# 04_Schematic.net
KiCad netlist of a schematic drawn in Altium Designer
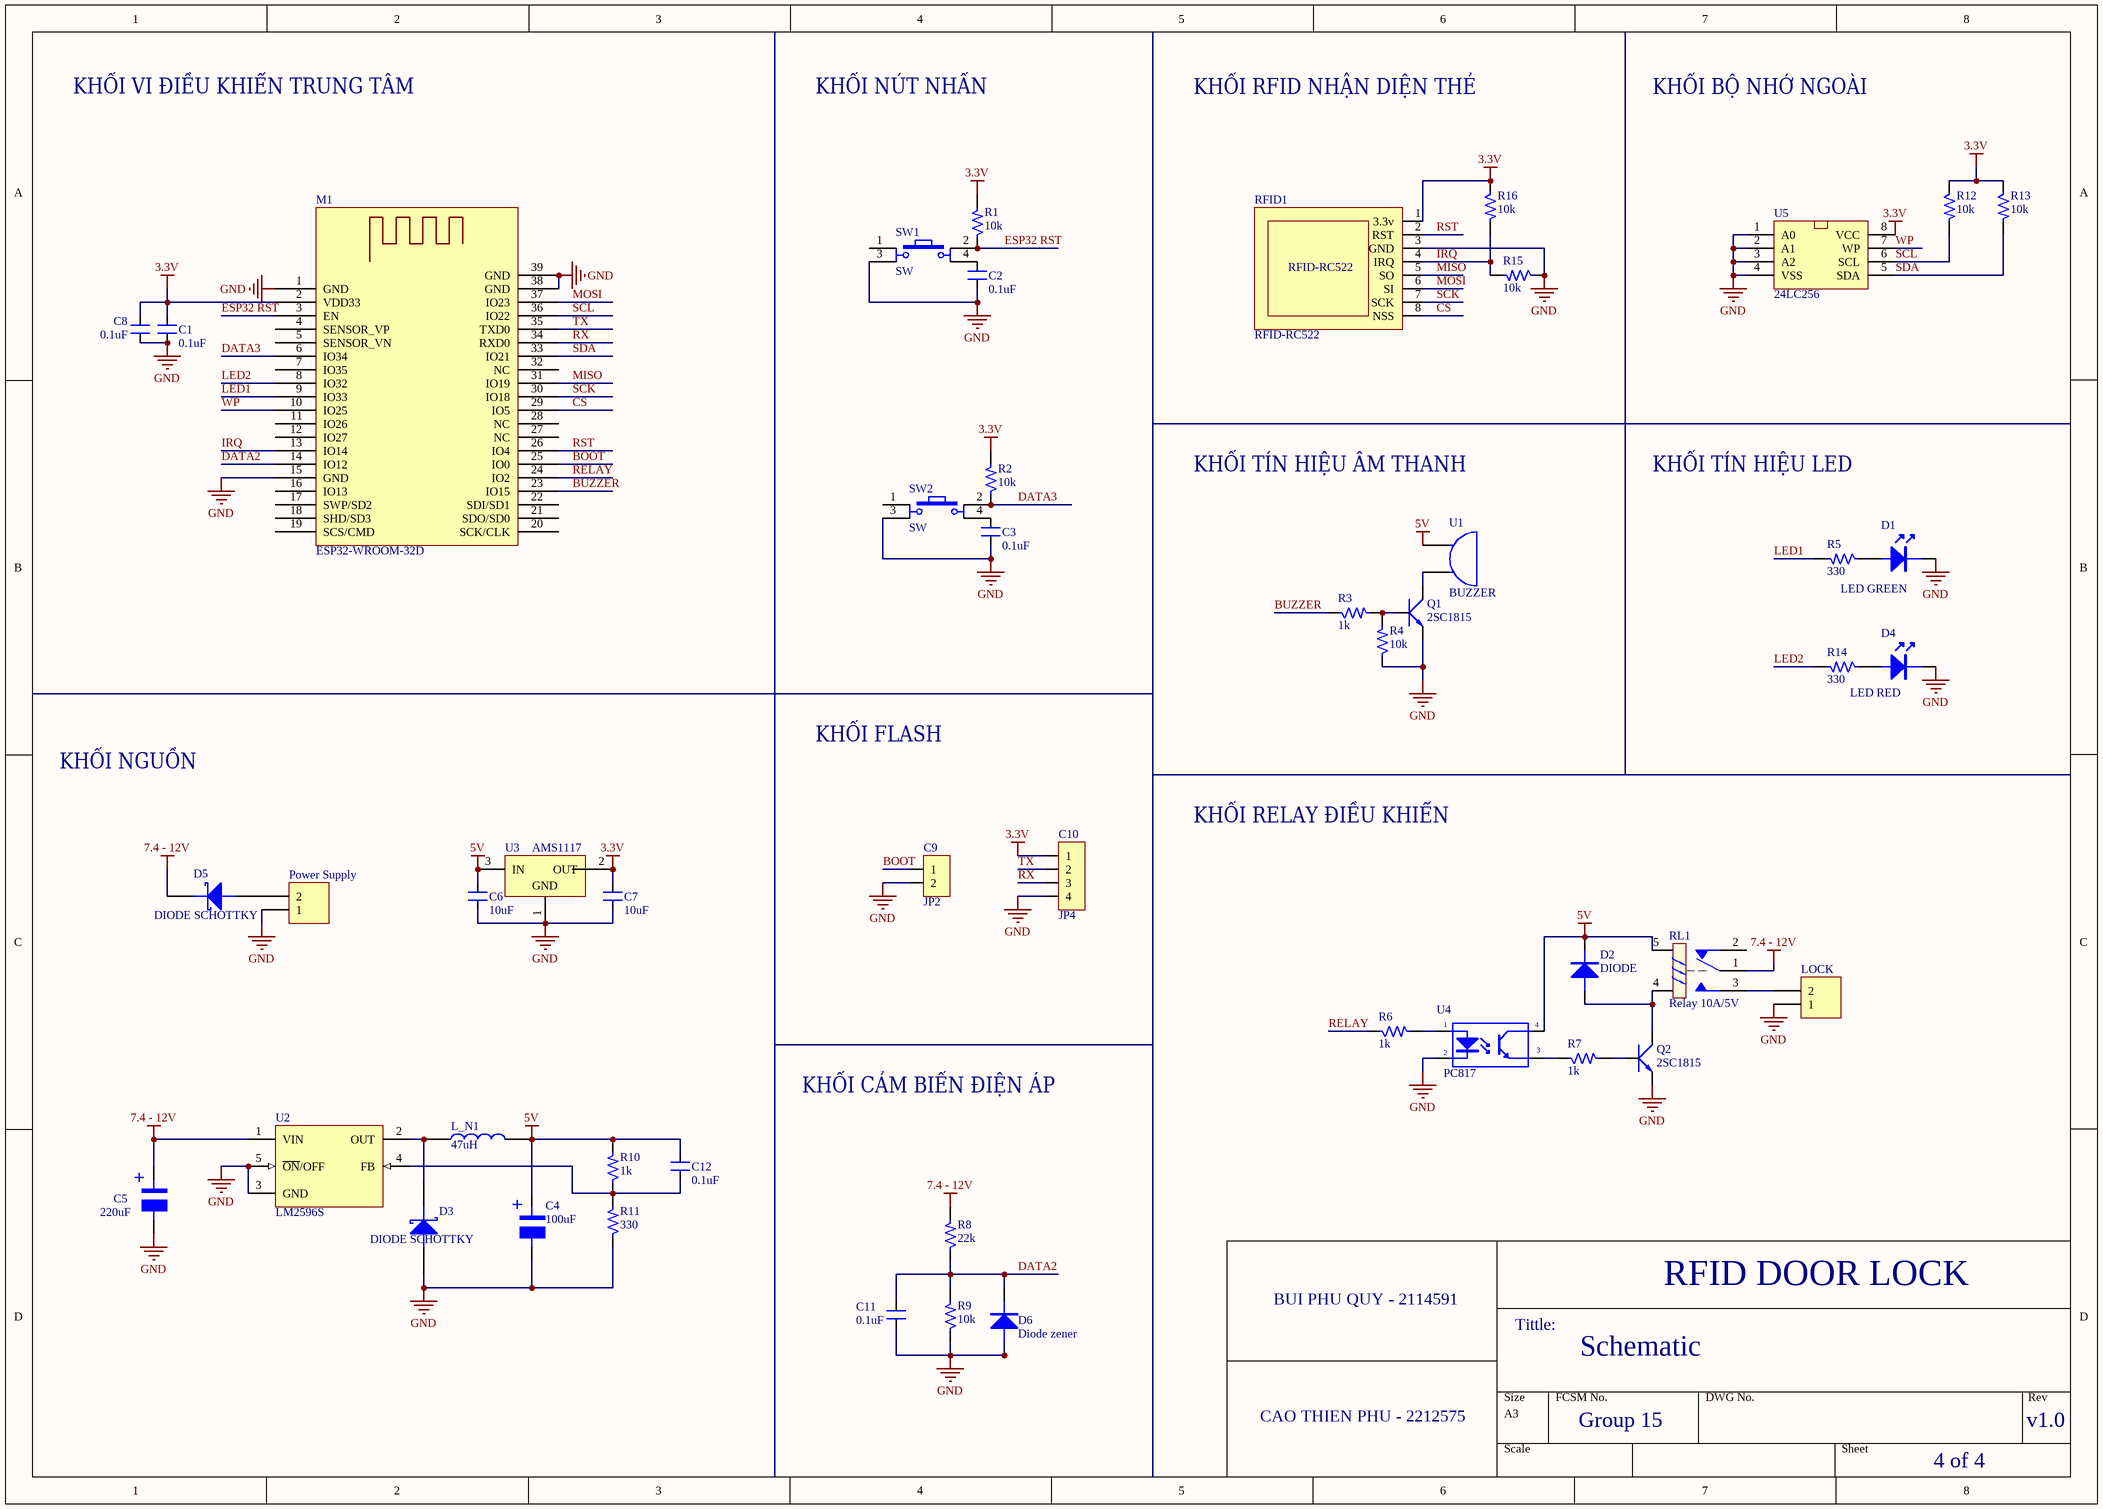
[diagram p0: 04.Schematic.SchDoc]

(export (version "E")
  (design (tool "Eeschema 10.0.6"))
  (components
    (comp (ref "C1")
      (value "0.1uF")
      (footprint "SMD CAP 0805")
      (description "Cap np W0.4")
      (libsource (lib "KhanhBK_Library_4") (part "CN4"))
    )
    (comp (ref "C2")
      (value "0.1uF")
      (footprint "SMD CAP 0805")
      (description "Cap np W0.4")
      (libsource (lib "KhanhBK_Library_4") (part "CN4"))
    )
    (comp (ref "C3")
      (value "0.1uF")
      (footprint "SMD CAP 0805")
      (description "Cap np W0.4")
      (libsource (lib "KhanhBK_Library_4") (part "CN4"))
    )
    (comp (ref "C4")
      (value "100uF")
      (footprint "Cty1:100UF/16V_SMD")
      (libsource (lib "Devzone_SCHLib") (part "Cap100uF_SMD"))
    )
    (comp (ref "C5")
      (value "220uF")
      (footprint "Cty1:100UF/16V_SMD")
      (libsource (lib "Devzone_SCHLib") (part "Cap100uF_SMD"))
    )
    (comp (ref "C6")
      (value "10uF")
      (footprint "SMD CAP 0805")
      (description "Cap np W0.4")
      (libsource (lib "KhanhBK_Library_4") (part "CN4"))
    )
    (comp (ref "C7")
      (value "10uF")
      (footprint "SMD CAP 0805")
      (description "Cap np W0.4")
      (libsource (lib "KhanhBK_Library_4") (part "CN4"))
    )
    (comp (ref "C8")
      (value "0.1uF")
      (footprint "SMD CAP 0805")
      (description "Cap np W0.4")
      (libsource (lib "KhanhBK_Library_4") (part "CN4"))
    )
    (comp (ref "C9")
      (value "JP2")
      (footprint "JP2-C1T")
      (description "WR-PHD 2.54 mm Angled Socket Header")
      (fields
        (field (name "MANUFACTURER") "Würth Elektronik eiSos GmbH")
        (field (name "PARTNO") "613002143121")
        (field (name "CREATED BY") "Karrer Zheng")
      )
      (libsource (lib "KhanhBK_Library_4") (part "JP2"))
    )
    (comp (ref "C10")
      (value "JP4")
      (footprint "JP4-C1T")
      (description "WR-PHD 2.54 mm Angled Socket Header")
      (fields
        (field (name "MANUFACTURER") "Würth Elektronik eiSos GmbH")
        (field (name "PARTNO") "613004143121")
        (field (name "CREATED BY") "Karrer Zheng")
      )
      (libsource (lib "KhanhBK_Library_4") (part "JP4"))
    )
    (comp (ref "C11")
      (value "0.1uF")
      (footprint "SMD CAP 0805")
      (description "Cap np W0.4")
      (libsource (lib "KhanhBK_Library_4") (part "CN4"))
    )
    (comp (ref "C12")
      (value "0.1uF")
      (footprint "SMD CAP 0805")
      (description "Cap np W0.4")
      (libsource (lib "KhanhBK_Library_4") (part "CN4"))
    )
    (comp (ref "D1") (value "LED GREEN") (footprint "LED3mm") (libsource (lib "Devzone_SCHLib") (part "LED")))
    (comp (ref "D2")
      (value "DIODE")
      (footprint "LL4148 Diode")
      (description "Diode")
      (libsource (lib "Devzone_SCHLib") (part "DIODE"))
    )
    (comp (ref "D3")
      (value "DIODE SCHOTTKY")
      (footprint "SMD SS34")
      (description "Schottky Diode")
      (libsource (lib "Devzone_SCHLib") (part "DIODE SCHOTTKY"))
    )
    (comp (ref "D4") (value "LED RED") (footprint "LED3mm") (libsource (lib "Devzone_SCHLib") (part "LED")))
    (comp (ref "D5")
      (value "DIODE SCHOTTKY")
      (footprint "SMD SS34")
      (description "Schottky Diode")
      (libsource (lib "Devzone_SCHLib") (part "DIODE SCHOTTKY"))
    )
    (comp (ref "D6")
      (value "Diode zener")
      (footprint "LL4148 Diode")
      (description "Diode")
      (libsource (lib "Devzone_SCHLib") (part "DIODE"))
    )
    (comp (ref "LOCK")
      (value "DOMINO")
      (footprint "CON 2")
      (libsource (lib "KhanhBK_Library_4") (part "HEADER 2"))
    )
    (comp (ref "L_N1")
      (value "47uH")
      (footprint "SMD 12mmx8mm Inductor")
      (libsource (lib "Devzone_SCHLib") (part "INDUCTOR1"))
    )
    (comp (ref "M1")
      (value "ESP32-WROOM-32D")
      (footprint "ESP32-WROOM-32")
      (description "ESP32")
      (libsource (lib "KhanhBK_SCH_Lib_5") (part "WIFI_ESP32-WROVER"))
    )
    (comp (ref "Power Supply")
      (value "DOMINO")
      (footprint "CON 2")
      (libsource (lib "KhanhBK_Library_4") (part "HEADER 2"))
    )
    (comp (ref "Q1")
      (value "2SC1815")
      (footprint "SOT23-321")
      (description "NPN 600mW, ECB")
      (libsource (lib "KhanhBK_Library_4") (part "2SC1815"))
    )
    (comp (ref "Q2")
      (value "2SC1815")
      (footprint "SOT23-321")
      (description "NPN 600mW, ECB")
      (libsource (lib "KhanhBK_Library_4") (part "2SC1815"))
    )
    (comp (ref "R1")
      (value "10k")
      (footprint "SM-0805")
      (description "Resistor 1/4W")
      (libsource (lib "Devzone_SCHLib") (part "Res"))
    )
    (comp (ref "R2")
      (value "10k")
      (footprint "SM-0805")
      (description "Resistor 1/4W")
      (libsource (lib "Devzone_SCHLib") (part "Res"))
    )
    (comp (ref "R3")
      (value "1k")
      (footprint "SM-0805")
      (description "Resistor 1/4W")
      (libsource (lib "Devzone_SCHLib") (part "Res"))
    )
    (comp (ref "R4")
      (value "10k")
      (footprint "SM-0805")
      (description "Resistor 1/4W")
      (libsource (lib "Devzone_SCHLib") (part "Res"))
    )
    (comp (ref "R5")
      (value "330")
      (footprint "SM-0805")
      (description "Resistor 1/4W")
      (libsource (lib "Devzone_SCHLib") (part "Res"))
    )
    (comp (ref "R6")
      (value "1k")
      (footprint "SM-0805")
      (description "Resistor 1/4W")
      (libsource (lib "Devzone_SCHLib") (part "Res"))
    )
    (comp (ref "R7")
      (value "1k")
      (footprint "SM-0805")
      (description "Resistor 1/4W")
      (libsource (lib "Devzone_SCHLib") (part "Res"))
    )
    (comp (ref "R8")
      (value "22k")
      (footprint "SM-0805")
      (description "Resistor 1/4W")
      (libsource (lib "Devzone_SCHLib") (part "Res"))
    )
    (comp (ref "R9")
      (value "10k")
      (footprint "SM-0805")
      (description "Resistor 1/4W")
      (libsource (lib "Devzone_SCHLib") (part "Res"))
    )
    (comp (ref "R10")
      (value "1k")
      (footprint "SM-0805")
      (description "Resistor 1/4W")
      (libsource (lib "Devzone_SCHLib") (part "Res"))
    )
    (comp (ref "R11")
      (value "330")
      (footprint "SM-0805")
      (description "Resistor 1/4W")
      (libsource (lib "Devzone_SCHLib") (part "Res"))
    )
    (comp (ref "R12")
      (value "10k")
      (footprint "SM-0805")
      (description "Resistor 1/4W")
      (libsource (lib "Devzone_SCHLib") (part "Res"))
    )
    (comp (ref "R13")
      (value "10k")
      (footprint "SM-0805")
      (description "Resistor 1/4W")
      (libsource (lib "Devzone_SCHLib") (part "Res"))
    )
    (comp (ref "R14")
      (value "330")
      (footprint "SM-0805")
      (description "Resistor 1/4W")
      (libsource (lib "Devzone_SCHLib") (part "Res"))
    )
    (comp (ref "R15")
      (value "10k")
      (footprint "SM-0805")
      (description "Resistor 1/4W")
      (libsource (lib "Devzone_SCHLib") (part "Res"))
    )
    (comp (ref "R16")
      (value "10k")
      (footprint "SM-0805")
      (description "Resistor 1/4W")
      (libsource (lib "Devzone_SCHLib") (part "Res"))
    )
    (comp (ref "RFID1")
      (value "RFID-RC522")
      (footprint "RFID-RC522-BOARD")
      (libsource (lib "SCH_Lib_Devzone") (part "RFID"))
    )
    (comp (ref "RL1")
      (value "Relay 10A/5V")
      (footprint "RL_SPDT_10A")
      (description "Relay SPDT,10A - 12VDC 5 Pin")
      (libsource (lib "KhanhBK_Library_4") (part "Relay 1"))
    )
    (comp (ref "SW1")
      (value "SW")
      (footprint "SW4")
      (description "Switch button 4 pin")
      (libsource (lib "Devzone_SCHLib") (part "SW4"))
    )
    (comp (ref "SW2")
      (value "SW")
      (footprint "SW4")
      (description "Switch button 4 pin")
      (libsource (lib "Devzone_SCHLib") (part "SW4"))
    )
    (comp (ref "U1")
      (value "BUZZER")
      (footprint "BUZZER 5V")
      (description "Buzzer")
      (libsource (lib "Devzone_SCHLib") (part "BUZZER"))
    )
    (comp (ref "U2")
      (value "LM2596S")
      (footprint "TO263-5_Via40/10mil")
      (description "SIMPLE SWITCHER; 3A Step-Down Voltage Regulator")
      (fields
        (field (name "PARTNUMBER") "LM2596S-5.0")
        (field (name "MANUFACTURER") "National Semiconductor")
        (field (name "PUBLISHER") "Altium Limited")
      )
      (libsource (lib "KhanhBK_Library_4") (part "LM2596"))
    )
    (comp (ref "U3")
      (value "AMS1117")
      (footprint "SOT223")
      (libsource (lib "KhanhBK_Library_4") (part "AMS117"))
    )
    (comp (ref "U4")
      (value "PC817")
      (footprint "DIP4/W0.3")
      (description "Single Opto")
      (libsource (lib "Devzone_SCHLib") (part "PC817_1"))
    )
    (comp (ref "U5")
      (value "24LC256")
      (footprint "SOP8_L")
      (description "256KBit I2C CMOS Serial EEPROM")
      (libsource (lib "KhanhBK_SCH_Lib_5") (part "24LC256"))
    )
  )
  (nets
    (net (code "1") (name "/BOOT") (class "Default")
      (node (ref "C9") (pin "1") (pinfunction "1_1") (pintype "passive"))
      (node (ref "M1") (pin "25") (pinfunction "IO0_25") (pintype "passive"))
    )
    (net (code "2") (name "/BUZZER") (class "Default")
      (node (ref "M1") (pin "23") (pinfunction "IO15_23") (pintype "passive"))
      (node (ref "R3") (pin "1") (pinfunction "1_1") (pintype "passive"))
    )
    (net (code "3") (name "/CS") (class "Default")
      (node (ref "M1") (pin "29") (pinfunction "IO5_29") (pintype "passive"))
      (node (ref "RFID1") (pin "8") (pinfunction "NSS_8") (pintype "passive"))
    )
    (net (code "4") (name "/DATA2") (class "Default")
      (node (ref "C11") (pin "2") (pinfunction "2_2") (pintype "passive"))
      (node (ref "D6") (pin "2") (pinfunction "2_2") (pintype "passive"))
      (node (ref "M1") (pin "14") (pinfunction "IO12_14") (pintype "passive"))
      (node (ref "R8") (pin "1") (pinfunction "1_1") (pintype "passive"))
      (node (ref "R9") (pin "2") (pinfunction "2_2") (pintype "passive"))
    )
    (net (code "5") (name "/DATA3") (class "Default")
      (node (ref "M1") (pin "6") (pinfunction "IO34_6") (pintype "passive"))
      (node (ref "R2") (pin "1") (pinfunction "1_1") (pintype "passive"))
      (node (ref "SW2") (pin "2") (pintype "passive"))
    )
    (net (code "6") (name "/ESP32 RST") (class "Default")
      (node (ref "M1") (pin "3") (pinfunction "EN_3") (pintype "passive"))
      (node (ref "R1") (pin "1") (pinfunction "1_1") (pintype "passive"))
      (node (ref "SW1") (pin "2") (pintype "passive"))
    )
    (net (code "7") (name "/IRQ") (class "Default")
      (node (ref "M1") (pin "13") (pinfunction "IO14_13") (pintype "passive"))
      (node (ref "R15") (pin "2") (pinfunction "2_2") (pintype "passive"))
      (node (ref "R16") (pin "2") (pinfunction "2_2") (pintype "passive"))
      (node (ref "RFID1") (pin "4") (pinfunction "IRQ_4") (pintype "passive"))
    )
    (net (code "8") (name "/LED1") (class "Default")
      (node (ref "M1") (pin "9") (pinfunction "IO33_9") (pintype "passive"))
      (node (ref "R5") (pin "2") (pinfunction "2_2") (pintype "passive"))
    )
    (net (code "9") (name "/LED2") (class "Default")
      (node (ref "M1") (pin "8") (pinfunction "IO32_8") (pintype "passive"))
      (node (ref "R14") (pin "2") (pinfunction "2_2") (pintype "passive"))
    )
    (net (code "10") (name "/MISO") (class "Default")
      (node (ref "M1") (pin "31") (pinfunction "IO19_31") (pintype "passive"))
      (node (ref "RFID1") (pin "5") (pinfunction "SO_5") (pintype "passive"))
    )
    (net (code "11") (name "/MOSI") (class "Default")
      (node (ref "M1") (pin "37") (pinfunction "IO23_37") (pintype "passive"))
      (node (ref "RFID1") (pin "6") (pinfunction "SI_6") (pintype "passive"))
    )
    (net (code "12") (name "/RELAY") (class "Default")
      (node (ref "M1") (pin "24") (pinfunction "IO2_24") (pintype "passive"))
      (node (ref "R6") (pin "1") (pinfunction "1_1") (pintype "passive"))
    )
    (net (code "13") (name "/RST") (class "Default")
      (node (ref "M1") (pin "26") (pinfunction "IO4_26") (pintype "passive"))
      (node (ref "RFID1") (pin "2") (pinfunction "RST_2") (pintype "passive"))
    )
    (net (code "14") (name "/RX") (class "Default")
      (node (ref "C10") (pin "3") (pinfunction "3_3") (pintype "passive"))
      (node (ref "M1") (pin "34") (pinfunction "RXD0_34") (pintype "passive"))
    )
    (net (code "15") (name "/SCK") (class "Default")
      (node (ref "M1") (pin "30") (pinfunction "IO18_30") (pintype "passive"))
      (node (ref "RFID1") (pin "7") (pinfunction "SCK_7") (pintype "passive"))
    )
    (net (code "16") (name "/SCL") (class "Default")
      (node (ref "M1") (pin "36") (pinfunction "IO22_36") (pintype "passive"))
      (node (ref "R12") (pin "2") (pinfunction "2_2") (pintype "passive"))
      (node (ref "U5") (pin "6") (pinfunction "SCL_6") (pintype "passive"))
    )
    (net (code "17") (name "/SDA") (class "Default")
      (node (ref "M1") (pin "33") (pinfunction "IO21_33") (pintype "passive"))
      (node (ref "R13") (pin "2") (pinfunction "2_2") (pintype "passive"))
      (node (ref "U5") (pin "5") (pinfunction "SDA_5") (pintype "passive"))
    )
    (net (code "18") (name "/TX") (class "Default")
      (node (ref "C10") (pin "2") (pinfunction "2_2") (pintype "passive"))
      (node (ref "M1") (pin "35") (pinfunction "TXD0_35") (pintype "passive"))
    )
    (net (code "19") (name "/WP") (class "Default")
      (node (ref "M1") (pin "10") (pinfunction "IO25_10") (pintype "passive"))
      (node (ref "U5") (pin "7") (pinfunction "WP_7") (pintype "passive"))
    )
    (net (code "20") (name "3.3V") (class "Default")
      (node (ref "C1") (pin "2") (pinfunction "2_2") (pintype "passive"))
      (node (ref "C10") (pin "1") (pinfunction "1_1") (pintype "passive"))
      (node (ref "C7") (pin "2") (pinfunction "2_2") (pintype "passive"))
      (node (ref "C8") (pin "2") (pinfunction "2_2") (pintype "passive"))
      (node (ref "M1") (pin "2") (pinfunction "VDD33_2") (pintype "passive"))
      (node (ref "R1") (pin "2") (pinfunction "2_2") (pintype "passive"))
      (node (ref "R12") (pin "1") (pinfunction "1_1") (pintype "passive"))
      (node (ref "R13") (pin "1") (pinfunction "1_1") (pintype "passive"))
      (node (ref "R16") (pin "1") (pinfunction "1_1") (pintype "passive"))
      (node (ref "R2") (pin "2") (pinfunction "2_2") (pintype "passive"))
      (node (ref "RFID1") (pin "1") (pinfunction "3.3v_1") (pintype "passive"))
      (node (ref "U3") (pin "2") (pinfunction "OUT_2") (pintype "power_in"))
      (node (ref "U3") (pin "4") (pinfunction "4_4") (pintype "passive"))
      (node (ref "U5") (pin "8") (pinfunction "VCC_8") (pintype "passive"))
    )
    (net (code "21") (name "5V") (class "Default")
      (node (ref "C12") (pin "2") (pinfunction "2_2") (pintype "passive"))
      (node (ref "C4") (pin "1") (pinfunction "1_1") (pintype "passive"))
      (node (ref "C6") (pin "2") (pinfunction "2_2") (pintype "passive"))
      (node (ref "D2") (pin "2") (pinfunction "2_2") (pintype "passive"))
      (node (ref "L_N1") (pin "2") (pinfunction "2_2") (pintype "passive"))
      (node (ref "R10") (pin "2") (pinfunction "2_2") (pintype "passive"))
      (node (ref "RL1") (pin "5") (pinfunction "5_5") (pintype "passive"))
      (node (ref "U1") (pin "1") (pinfunction "A_1") (pintype "passive"))
      (node (ref "U3") (pin "3") (pinfunction "IN_3") (pintype "power_in"))
      (node (ref "U4") (pin "4") (pinfunction "C_4") (pintype "passive"))
    )
    (net (code "22") (name "7.4 - 12V") (class "Default")
      (node (ref "C5") (pin "1") (pinfunction "1_1") (pintype "passive"))
      (node (ref "D5") (pin "2") (pinfunction "K_2") (pintype "passive"))
      (node (ref "R8") (pin "2") (pinfunction "2_2") (pintype "passive"))
      (node (ref "RL1") (pin "1") (pinfunction "1_1") (pintype "passive"))
      (node (ref "U2") (pin "1") (pinfunction "VIN_1") (pintype "power_in"))
    )
    (net (code "23") (name "GND") (class "Default")
      (node (ref "C1") (pin "1") (pinfunction "1_1") (pintype "passive"))
      (node (ref "C10") (pin "4") (pinfunction "4_4") (pintype "passive"))
      (node (ref "C11") (pin "1") (pinfunction "1_1") (pintype "passive"))
      (node (ref "C2") (pin "1") (pinfunction "1_1") (pintype "passive"))
      (node (ref "C3") (pin "1") (pinfunction "1_1") (pintype "passive"))
      (node (ref "C4") (pin "2") (pinfunction "2_2") (pintype "passive"))
      (node (ref "C5") (pin "2") (pinfunction "2_2") (pintype "passive"))
      (node (ref "C6") (pin "1") (pinfunction "1_1") (pintype "passive"))
      (node (ref "C7") (pin "1") (pinfunction "1_1") (pintype "passive"))
      (node (ref "C8") (pin "1") (pinfunction "1_1") (pintype "passive"))
      (node (ref "C9") (pin "2") (pinfunction "2_2") (pintype "passive"))
      (node (ref "D1") (pin "2") (pinfunction "2_2") (pintype "passive"))
      (node (ref "D3") (pin "1") (pinfunction "A_1") (pintype "passive"))
      (node (ref "D4") (pin "2") (pinfunction "2_2") (pintype "passive"))
      (node (ref "D6") (pin "1") (pinfunction "1_1") (pintype "passive"))
      (node (ref "LOCK") (pin "1") (pinfunction "1_1") (pintype "passive"))
      (node (ref "M1") (pin "1") (pinfunction "GND_1") (pintype "passive"))
      (node (ref "M1") (pin "15") (pinfunction "GND_15") (pintype "passive"))
      (node (ref "M1") (pin "38") (pinfunction "GND_38") (pintype "passive"))
      (node (ref "M1") (pin "39") (pinfunction "GND_39") (pintype "passive"))
      (node (ref "Power Supply") (pin "1") (pinfunction "1_1") (pintype "passive"))
      (node (ref "Q1") (pin "1") (pinfunction "E_1") (pintype "passive"))
      (node (ref "Q2") (pin "1") (pinfunction "E_1") (pintype "passive"))
      (node (ref "R11") (pin "1") (pinfunction "1_1") (pintype "passive"))
      (node (ref "R15") (pin "1") (pinfunction "1_1") (pintype "passive"))
      (node (ref "R4") (pin "1") (pinfunction "1_1") (pintype "passive"))
      (node (ref "R9") (pin "1") (pinfunction "1_1") (pintype "passive"))
      (node (ref "RFID1") (pin "3") (pinfunction "GND_3") (pintype "passive"))
      (node (ref "SW1") (pin "3") (pintype "passive"))
      (node (ref "SW2") (pin "3") (pintype "passive"))
      (node (ref "U2") (pin "3") (pinfunction "GND_3") (pintype "power_in"))
      (node (ref "U2") (pin "5") (pinfunction "~{ON}/OFF_5") (pintype "input"))
      (node (ref "U3") (pin "1") (pinfunction "GND_1") (pintype "power_in"))
      (node (ref "U4") (pin "2") (pinfunction "K_2") (pintype "passive"))
      (node (ref "U5") (pin "1") (pinfunction "A0_1") (pintype "passive"))
      (node (ref "U5") (pin "2") (pinfunction "A1_2") (pintype "passive"))
      (node (ref "U5") (pin "3") (pinfunction "A2_3") (pintype "passive"))
      (node (ref "U5") (pin "4") (pinfunction "VSS_4") (pintype "passive"))
    )
    (net (code "24") (name "Net-(C2-Pad2)") (class "Default")
      (node (ref "C2") (pin "2") (pinfunction "2_2") (pintype "passive"))
      (node (ref "SW1") (pin "4") (pintype "passive"))
    )
    (net (code "25") (name "Net-(C3-Pad2)") (class "Default")
      (node (ref "C3") (pin "2") (pinfunction "2_2") (pintype "passive"))
      (node (ref "SW2") (pin "4") (pintype "passive"))
    )
    (net (code "26") (name "Net-(D1-Pad1)") (class "Default")
      (node (ref "D1") (pin "1") (pinfunction "1_1") (pintype "passive"))
      (node (ref "R5") (pin "1") (pinfunction "1_1") (pintype "passive"))
    )
    (net (code "27") (name "Net-(D3-K)") (class "Default")
      (node (ref "D3") (pin "2") (pinfunction "K_2") (pintype "passive"))
      (node (ref "L_N1") (pin "1") (pinfunction "1_1") (pintype "passive"))
      (node (ref "U2") (pin "2") (pinfunction "OUT_2") (pintype "power_in"))
    )
    (net (code "28") (name "Net-(D4-Pad1)") (class "Default")
      (node (ref "D4") (pin "1") (pinfunction "1_1") (pintype "passive"))
      (node (ref "R14") (pin "1") (pinfunction "1_1") (pintype "passive"))
    )
    (net (code "29") (name "Net-(D5-A)") (class "Default")
      (node (ref "D5") (pin "1") (pinfunction "A_1") (pintype "passive"))
      (node (ref "Power Supply") (pin "2") (pinfunction "2_2") (pintype "passive"))
    )
    (net (code "30") (name "Net-(LOCK-Pad2)") (class "Default")
      (node (ref "LOCK") (pin "2") (pinfunction "2_2") (pintype "passive"))
      (node (ref "RL1") (pin "3") (pinfunction "3_3") (pintype "passive"))
    )
    (net (code "31") (name "Net-(Q1-B)") (class "Default")
      (node (ref "Q1") (pin "3") (pinfunction "B_3") (pintype "passive"))
      (node (ref "R3") (pin "2") (pinfunction "2_2") (pintype "passive"))
      (node (ref "R4") (pin "2") (pinfunction "2_2") (pintype "passive"))
    )
    (net (code "32") (name "Net-(Q1-C)") (class "Default")
      (node (ref "Q1") (pin "2") (pinfunction "C_2") (pintype "passive"))
      (node (ref "U1") (pin "2") (pinfunction "B_2") (pintype "passive"))
    )
    (net (code "33") (name "Net-(Q2-B)") (class "Default")
      (node (ref "Q2") (pin "3") (pinfunction "B_3") (pintype "passive"))
      (node (ref "R7") (pin "2") (pinfunction "2_2") (pintype "passive"))
    )
    (net (code "34") (name "Net-(Q2-C)") (class "Default")
      (node (ref "D2") (pin "1") (pinfunction "1_1") (pintype "passive"))
      (node (ref "Q2") (pin "2") (pinfunction "C_2") (pintype "passive"))
      (node (ref "RL1") (pin "4") (pinfunction "4_4") (pintype "passive"))
    )
    (net (code "35") (name "Net-(U2-FB)") (class "Default")
      (node (ref "C12") (pin "1") (pinfunction "1_1") (pintype "passive"))
      (node (ref "R10") (pin "1") (pinfunction "1_1") (pintype "passive"))
      (node (ref "R11") (pin "2") (pinfunction "2_2") (pintype "passive"))
      (node (ref "U2") (pin "4") (pinfunction "FB_4") (pintype "input"))
    )
    (net (code "36") (name "Net-(U4-A)") (class "Default")
      (node (ref "R6") (pin "2") (pinfunction "2_2") (pintype "passive"))
      (node (ref "U4") (pin "1") (pinfunction "A_1") (pintype "passive"))
    )
    (net (code "37") (name "Net-(U4-E)") (class "Default")
      (node (ref "R7") (pin "1") (pinfunction "1_1") (pintype "passive"))
      (node (ref "U4") (pin "3") (pinfunction "E_3") (pintype "passive"))
    )
    (net (code "38") (name "unconnected-(M1-IO13-Pad16)") (class "Default")
      (node (ref "M1") (pin "16") (pinfunction "IO13_16") (pintype "passive"))
    )
    (net (code "39") (name "unconnected-(M1-IO26-Pad11)") (class "Default")
      (node (ref "M1") (pin "11") (pinfunction "IO26_11") (pintype "passive"))
    )
    (net (code "40") (name "unconnected-(M1-IO27-Pad12)") (class "Default")
      (node (ref "M1") (pin "12") (pinfunction "IO27_12") (pintype "passive"))
    )
    (net (code "41") (name "unconnected-(M1-IO35-Pad7)") (class "Default")
      (node (ref "M1") (pin "7") (pinfunction "IO35_7") (pintype "passive"))
    )
    (net (code "42") (name "unconnected-(M1-NC-Pad27)") (class "Default")
      (node (ref "M1") (pin "27") (pinfunction "NC_27") (pintype "passive"))
    )
    (net (code "43") (name "unconnected-(M1-NC-Pad28)") (class "Default")
      (node (ref "M1") (pin "28") (pinfunction "NC_28") (pintype "passive"))
    )
    (net (code "44") (name "unconnected-(M1-NC-Pad32)") (class "Default")
      (node (ref "M1") (pin "32") (pinfunction "NC_32") (pintype "passive"))
    )
    (net (code "45") (name "unconnected-(M1-SCK{slash}CLK-Pad20)") (class "Default")
      (node (ref "M1") (pin "20") (pinfunction "SCK/CLK_20") (pintype "passive"))
    )
    (net (code "46") (name "unconnected-(M1-SCS{slash}CMD-Pad19)") (class "Default")
      (node (ref "M1") (pin "19") (pinfunction "SCS/CMD_19") (pintype "passive"))
    )
    (net (code "47") (name "unconnected-(M1-SDI{slash}SD1-Pad22)") (class "Default")
      (node (ref "M1") (pin "22") (pinfunction "SDI/SD1_22") (pintype "passive"))
    )
    (net (code "48") (name "unconnected-(M1-SDO{slash}SD0-Pad21)") (class "Default")
      (node (ref "M1") (pin "21") (pinfunction "SDO/SD0_21") (pintype "passive"))
    )
    (net (code "49") (name "unconnected-(M1-SENSOR_VN-Pad5)") (class "Default")
      (node (ref "M1") (pin "5") (pinfunction "SENSOR_VN_5") (pintype "passive"))
    )
    (net (code "50") (name "unconnected-(M1-SENSOR_VP-Pad4)") (class "Default")
      (node (ref "M1") (pin "4") (pinfunction "SENSOR_VP_4") (pintype "passive"))
    )
    (net (code "51") (name "unconnected-(M1-SHD{slash}SD3-Pad18)") (class "Default")
      (node (ref "M1") (pin "18") (pinfunction "SHD/SD3_18") (pintype "passive"))
    )
    (net (code "52") (name "unconnected-(M1-SWP{slash}SD2-Pad17)") (class "Default")
      (node (ref "M1") (pin "17") (pinfunction "SWP/SD2_17") (pintype "passive"))
    )
    (net (code "53") (name "unconnected-(RL1-Pad2)") (class "Default")
      (node (ref "RL1") (pin "2") (pinfunction "2_2") (pintype "passive"))
    )
    (net (code "54") (name "unconnected-(SW1-Pad1)") (class "Default")
      (node (ref "SW1") (pin "1") (pintype "passive"))
    )
    (net (code "55") (name "unconnected-(SW2-Pad1)") (class "Default")
      (node (ref "SW2") (pin "1") (pintype "passive"))
    )
  )
)
